# port-expander.net
KiCad netlist of a schematic drawn in EAGLE
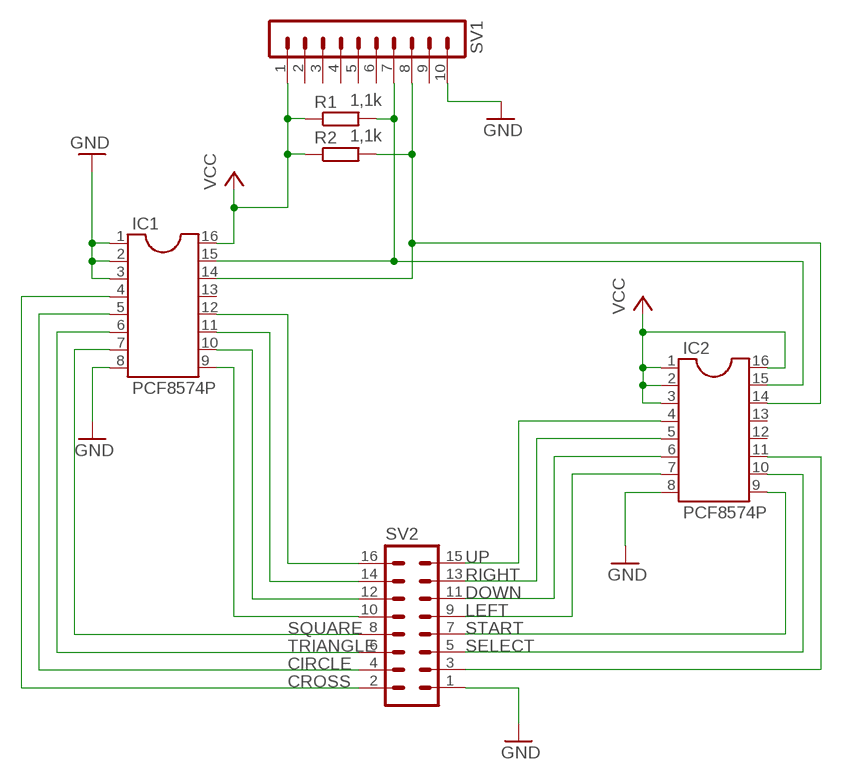
[diagram p0: schematic, sheet 1]

(export (version "E")
  (design (tool "Eeschema 10.0.6"))
  (components
    (comp (ref "IC1")
      (value "PCF8574P")
      (footprint "eagle-import:SOCKET-16")
      (libsource (lib "eagle-import") (part "DIL16S"))
    )
    (comp (ref "IC2")
      (value "PCF8574P")
      (footprint "eagle-import:SOCKET-16")
      (libsource (lib "eagle-import") (part "DIL16S"))
    )
    (comp (ref "R1")
      (value "1,1k")
      (footprint "eagle-import:0207_10")
      (libsource (lib "eagle-import") (part "R-EU_0207/10"))
    )
    (comp (ref "R2")
      (value "1,1k")
      (footprint "eagle-import:0207_10")
      (libsource (lib "eagle-import") (part "R-EU_0207/10"))
    )
    (comp (ref "SV1")
      (value "MA10-1")
      (footprint "eagle-import:MA10-1")
      (libsource (lib "eagle-import") (part "MA10-1"))
    )
    (comp (ref "SV2")
      (value "MA08-2")
      (footprint "eagle-import:MA08-2")
      (libsource (lib "eagle-import") (part "MA08-2"))
    )
  )
  (nets
    (net (code "1") (name "/CIRCLE") (class "Default")
      (node (ref "IC1") (pin "5") (pinfunction "5_5") (pintype "passive"))
      (node (ref "SV2") (pin "4") (pinfunction "4_4") (pintype "passive"))
    )
    (net (code "2") (name "/CROSS") (class "Default")
      (node (ref "IC1") (pin "4") (pinfunction "4_4") (pintype "passive"))
      (node (ref "SV2") (pin "2") (pinfunction "2_2") (pintype "passive"))
    )
    (net (code "3") (name "/DOWN") (class "Default")
      (node (ref "IC2") (pin "6") (pinfunction "6_6") (pintype "passive"))
      (node (ref "SV2") (pin "11") (pinfunction "11_11") (pintype "passive"))
    )
    (net (code "4") (name "/LEFT") (class "Default")
      (node (ref "IC2") (pin "7") (pinfunction "7_7") (pintype "passive"))
      (node (ref "SV2") (pin "9") (pinfunction "9_9") (pintype "passive"))
    )
    (net (code "5") (name "/RIGHT") (class "Default")
      (node (ref "IC2") (pin "5") (pinfunction "5_5") (pintype "passive"))
      (node (ref "SV2") (pin "13") (pinfunction "13_13") (pintype "passive"))
    )
    (net (code "6") (name "/SELECT") (class "Default")
      (node (ref "IC2") (pin "10") (pinfunction "10_10") (pintype "passive"))
      (node (ref "SV2") (pin "5") (pinfunction "5_5") (pintype "passive"))
    )
    (net (code "7") (name "/SQUARE") (class "Default")
      (node (ref "IC1") (pin "7") (pinfunction "7_7") (pintype "passive"))
      (node (ref "SV2") (pin "8") (pinfunction "8_8") (pintype "passive"))
    )
    (net (code "8") (name "/START") (class "Default")
      (node (ref "IC2") (pin "9") (pinfunction "9_9") (pintype "passive"))
      (node (ref "SV2") (pin "7") (pinfunction "7_7") (pintype "passive"))
    )
    (net (code "9") (name "/TRIANGLE") (class "Default")
      (node (ref "IC1") (pin "6") (pinfunction "6_6") (pintype "passive"))
      (node (ref "SV2") (pin "6") (pinfunction "6_6") (pintype "passive"))
    )
    (net (code "10") (name "/UP") (class "Default")
      (node (ref "IC2") (pin "4") (pinfunction "4_4") (pintype "passive"))
      (node (ref "SV2") (pin "15") (pinfunction "15_15") (pintype "passive"))
    )
    (net (code "11") (name "GND") (class "Default")
      (node (ref "IC1") (pin "1") (pinfunction "1_1") (pintype "passive"))
      (node (ref "IC1") (pin "2") (pinfunction "2_2") (pintype "passive"))
      (node (ref "IC1") (pin "3") (pinfunction "3_3") (pintype "passive"))
      (node (ref "IC1") (pin "8") (pinfunction "8_8") (pintype "passive"))
      (node (ref "IC2") (pin "8") (pinfunction "8_8") (pintype "passive"))
      (node (ref "SV1") (pin "10") (pinfunction "10_10") (pintype "passive"))
      (node (ref "SV2") (pin "1") (pinfunction "1_1") (pintype "passive"))
    )
    (net (code "12") (name "Net-(IC1-Pad9)") (class "Default")
      (node (ref "IC1") (pin "9") (pinfunction "9_9") (pintype "passive"))
      (node (ref "SV2") (pin "10") (pinfunction "10_10") (pintype "passive"))
    )
    (net (code "13") (name "Net-(IC1-Pad10)") (class "Default")
      (node (ref "IC1") (pin "10") (pinfunction "10_10") (pintype "passive"))
      (node (ref "SV2") (pin "12") (pinfunction "12_12") (pintype "passive"))
    )
    (net (code "14") (name "Net-(IC1-Pad11)") (class "Default")
      (node (ref "IC1") (pin "11") (pinfunction "11_11") (pintype "passive"))
      (node (ref "SV2") (pin "14") (pinfunction "14_14") (pintype "passive"))
    )
    (net (code "15") (name "Net-(IC1-Pad12)") (class "Default")
      (node (ref "IC1") (pin "12") (pinfunction "12_12") (pintype "passive"))
      (node (ref "SV2") (pin "16") (pinfunction "16_16") (pintype "passive"))
    )
    (net (code "16") (name "Net-(IC1-Pad14)") (class "Default")
      (node (ref "IC1") (pin "14") (pinfunction "14_14") (pintype "passive"))
      (node (ref "IC2") (pin "14") (pinfunction "14_14") (pintype "passive"))
      (node (ref "R2") (pin "2") (pinfunction "2_2") (pintype "passive"))
      (node (ref "SV1") (pin "8") (pinfunction "8_8") (pintype "passive"))
    )
    (net (code "17") (name "Net-(IC1-Pad15)") (class "Default")
      (node (ref "IC1") (pin "15") (pinfunction "15_15") (pintype "passive"))
      (node (ref "IC2") (pin "15") (pinfunction "15_15") (pintype "passive"))
      (node (ref "R1") (pin "2") (pinfunction "2_2") (pintype "passive"))
      (node (ref "SV1") (pin "7") (pinfunction "7_7") (pintype "passive"))
    )
    (net (code "18") (name "Net-(IC2-Pad11)") (class "Default")
      (node (ref "IC2") (pin "11") (pinfunction "11_11") (pintype "passive"))
      (node (ref "SV2") (pin "3") (pinfunction "3_3") (pintype "passive"))
    )
    (net (code "19") (name "VCC") (class "Default")
      (node (ref "IC1") (pin "16") (pinfunction "16_16") (pintype "passive"))
      (node (ref "IC2") (pin "1") (pinfunction "1_1") (pintype "passive"))
      (node (ref "IC2") (pin "16") (pinfunction "16_16") (pintype "passive"))
      (node (ref "IC2") (pin "2") (pinfunction "2_2") (pintype "passive"))
      (node (ref "IC2") (pin "3") (pinfunction "3_3") (pintype "passive"))
      (node (ref "R1") (pin "1") (pinfunction "1_1") (pintype "passive"))
      (node (ref "R2") (pin "1") (pinfunction "1_1") (pintype "passive"))
      (node (ref "SV1") (pin "1") (pinfunction "1_1") (pintype "passive"))
    )
    (net (code "20") (name "unconnected-(IC1-Pad13)") (class "Default")
      (node (ref "IC1") (pin "13") (pinfunction "13_13") (pintype "passive"))
    )
    (net (code "21") (name "unconnected-(IC2-Pad12)") (class "Default")
      (node (ref "IC2") (pin "12") (pinfunction "12_12") (pintype "passive"))
    )
    (net (code "22") (name "unconnected-(IC2-Pad13)") (class "Default")
      (node (ref "IC2") (pin "13") (pinfunction "13_13") (pintype "passive"))
    )
    (net (code "23") (name "unconnected-(SV1-Pad2)") (class "Default")
      (node (ref "SV1") (pin "2") (pinfunction "2_2") (pintype "passive"))
    )
    (net (code "24") (name "unconnected-(SV1-Pad3)") (class "Default")
      (node (ref "SV1") (pin "3") (pinfunction "3_3") (pintype "passive"))
    )
    (net (code "25") (name "unconnected-(SV1-Pad4)") (class "Default")
      (node (ref "SV1") (pin "4") (pinfunction "4_4") (pintype "passive"))
    )
    (net (code "26") (name "unconnected-(SV1-Pad5)") (class "Default")
      (node (ref "SV1") (pin "5") (pinfunction "5_5") (pintype "passive"))
    )
    (net (code "27") (name "unconnected-(SV1-Pad6)") (class "Default")
      (node (ref "SV1") (pin "6") (pinfunction "6_6") (pintype "passive"))
    )
    (net (code "28") (name "unconnected-(SV1-Pad9)") (class "Default")
      (node (ref "SV1") (pin "9") (pinfunction "9_9") (pintype "passive"))
    )
  )
)
